# R3Mkr12F_Solar.net
KiCad netlist of a schematic drawn in EAGLE
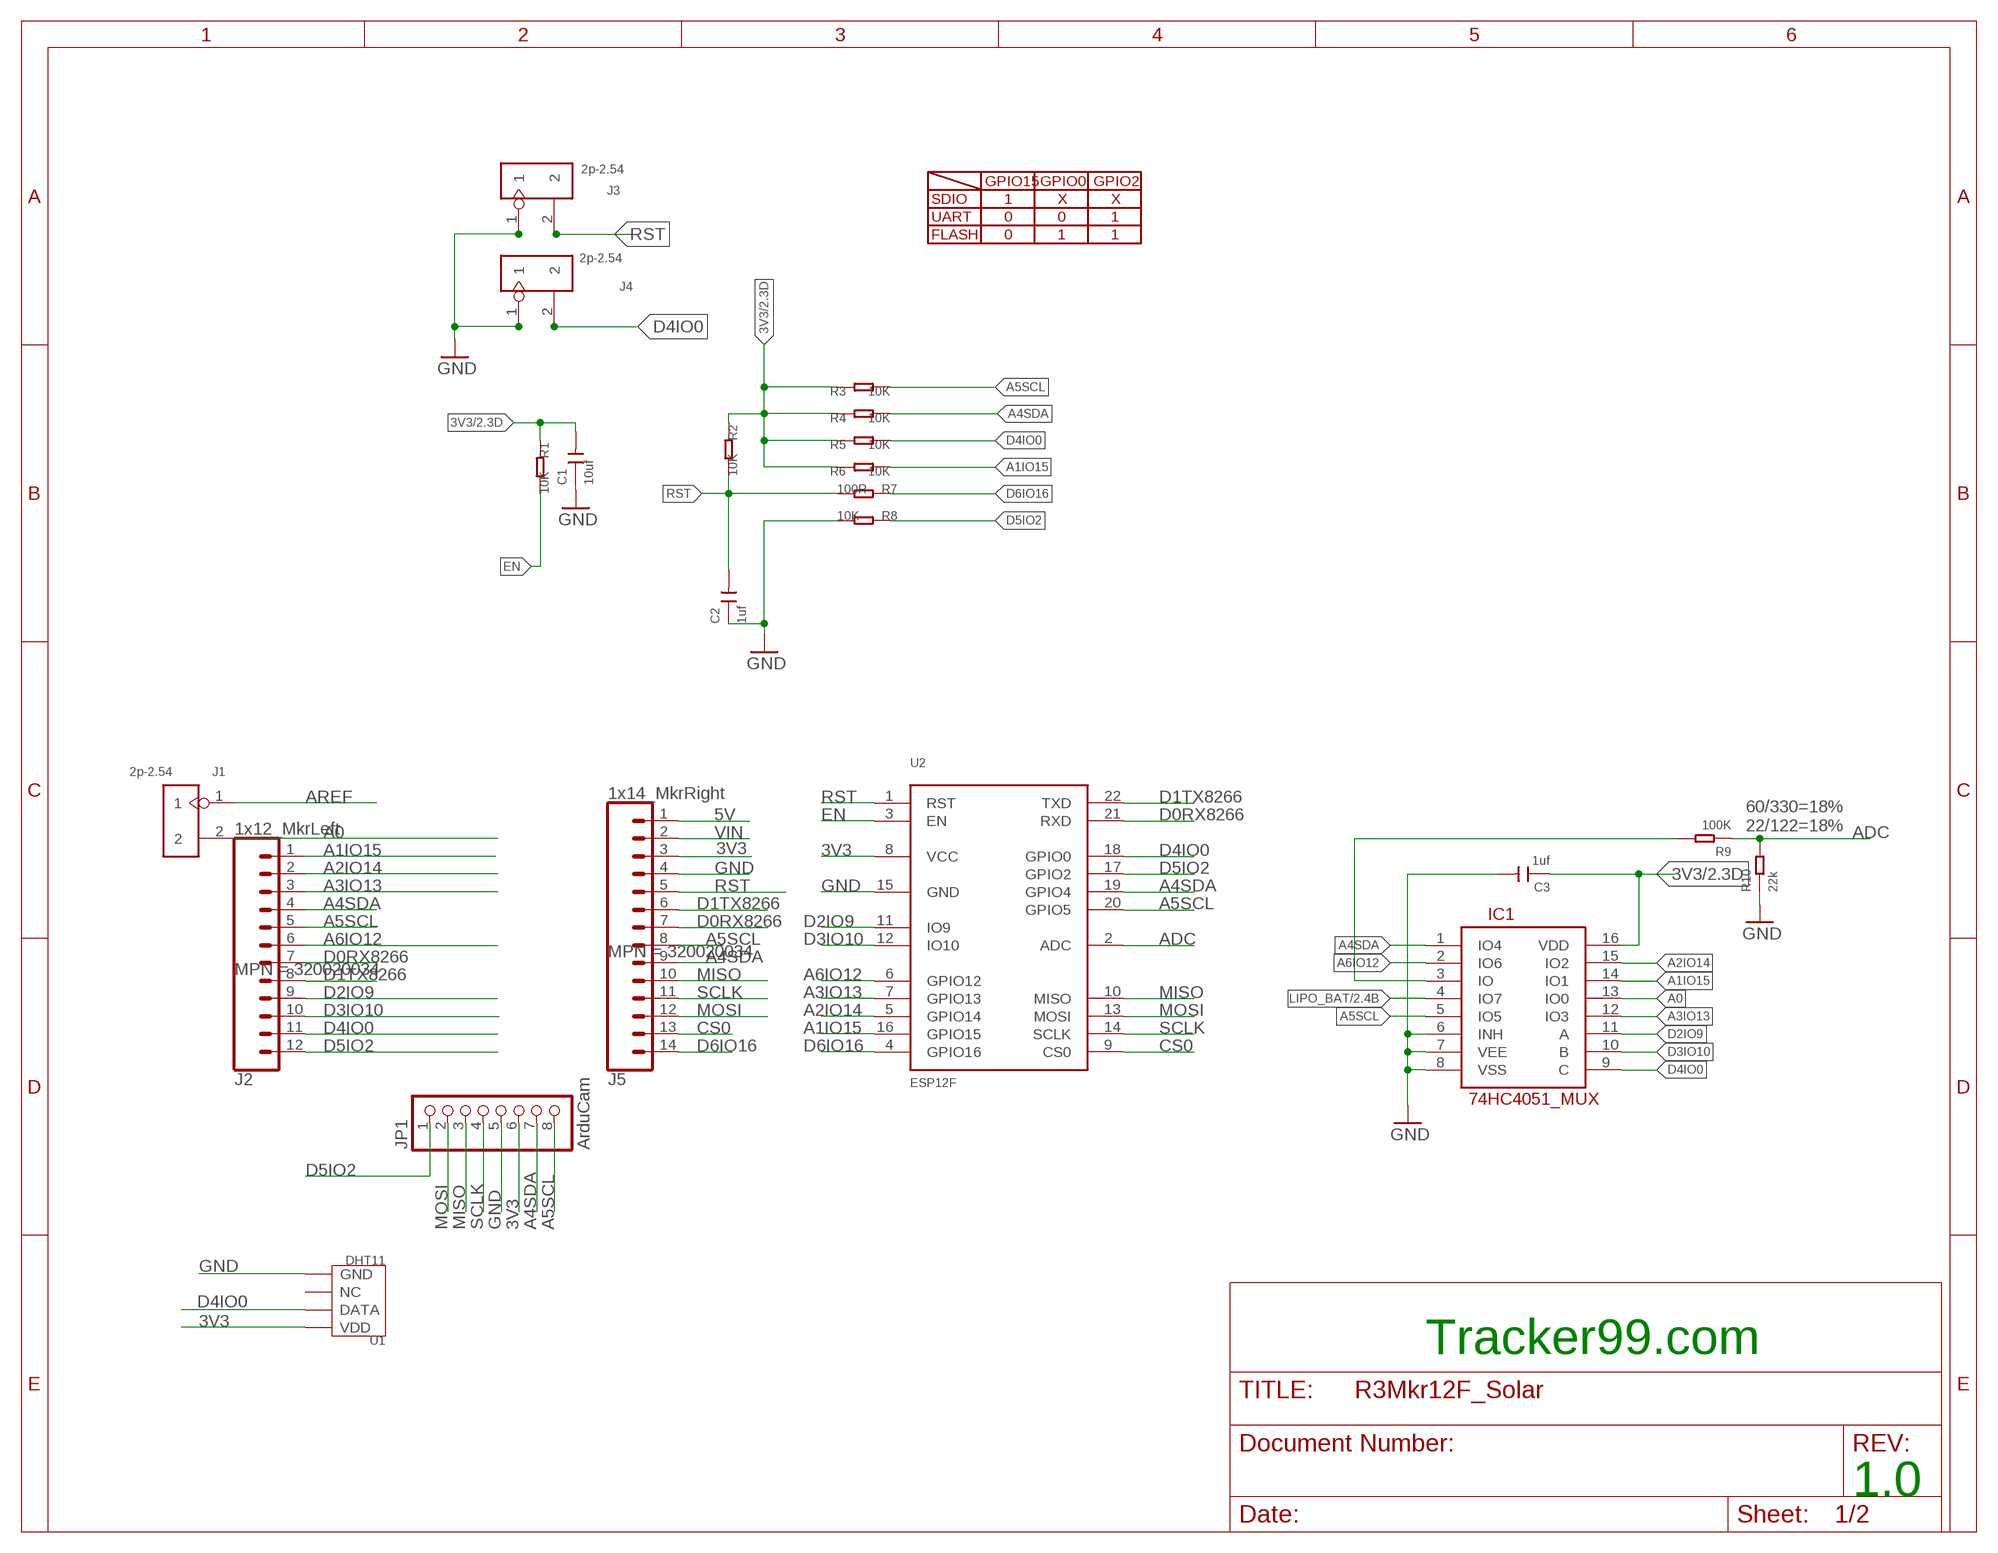
[diagram p0: schematic, sheet 1]
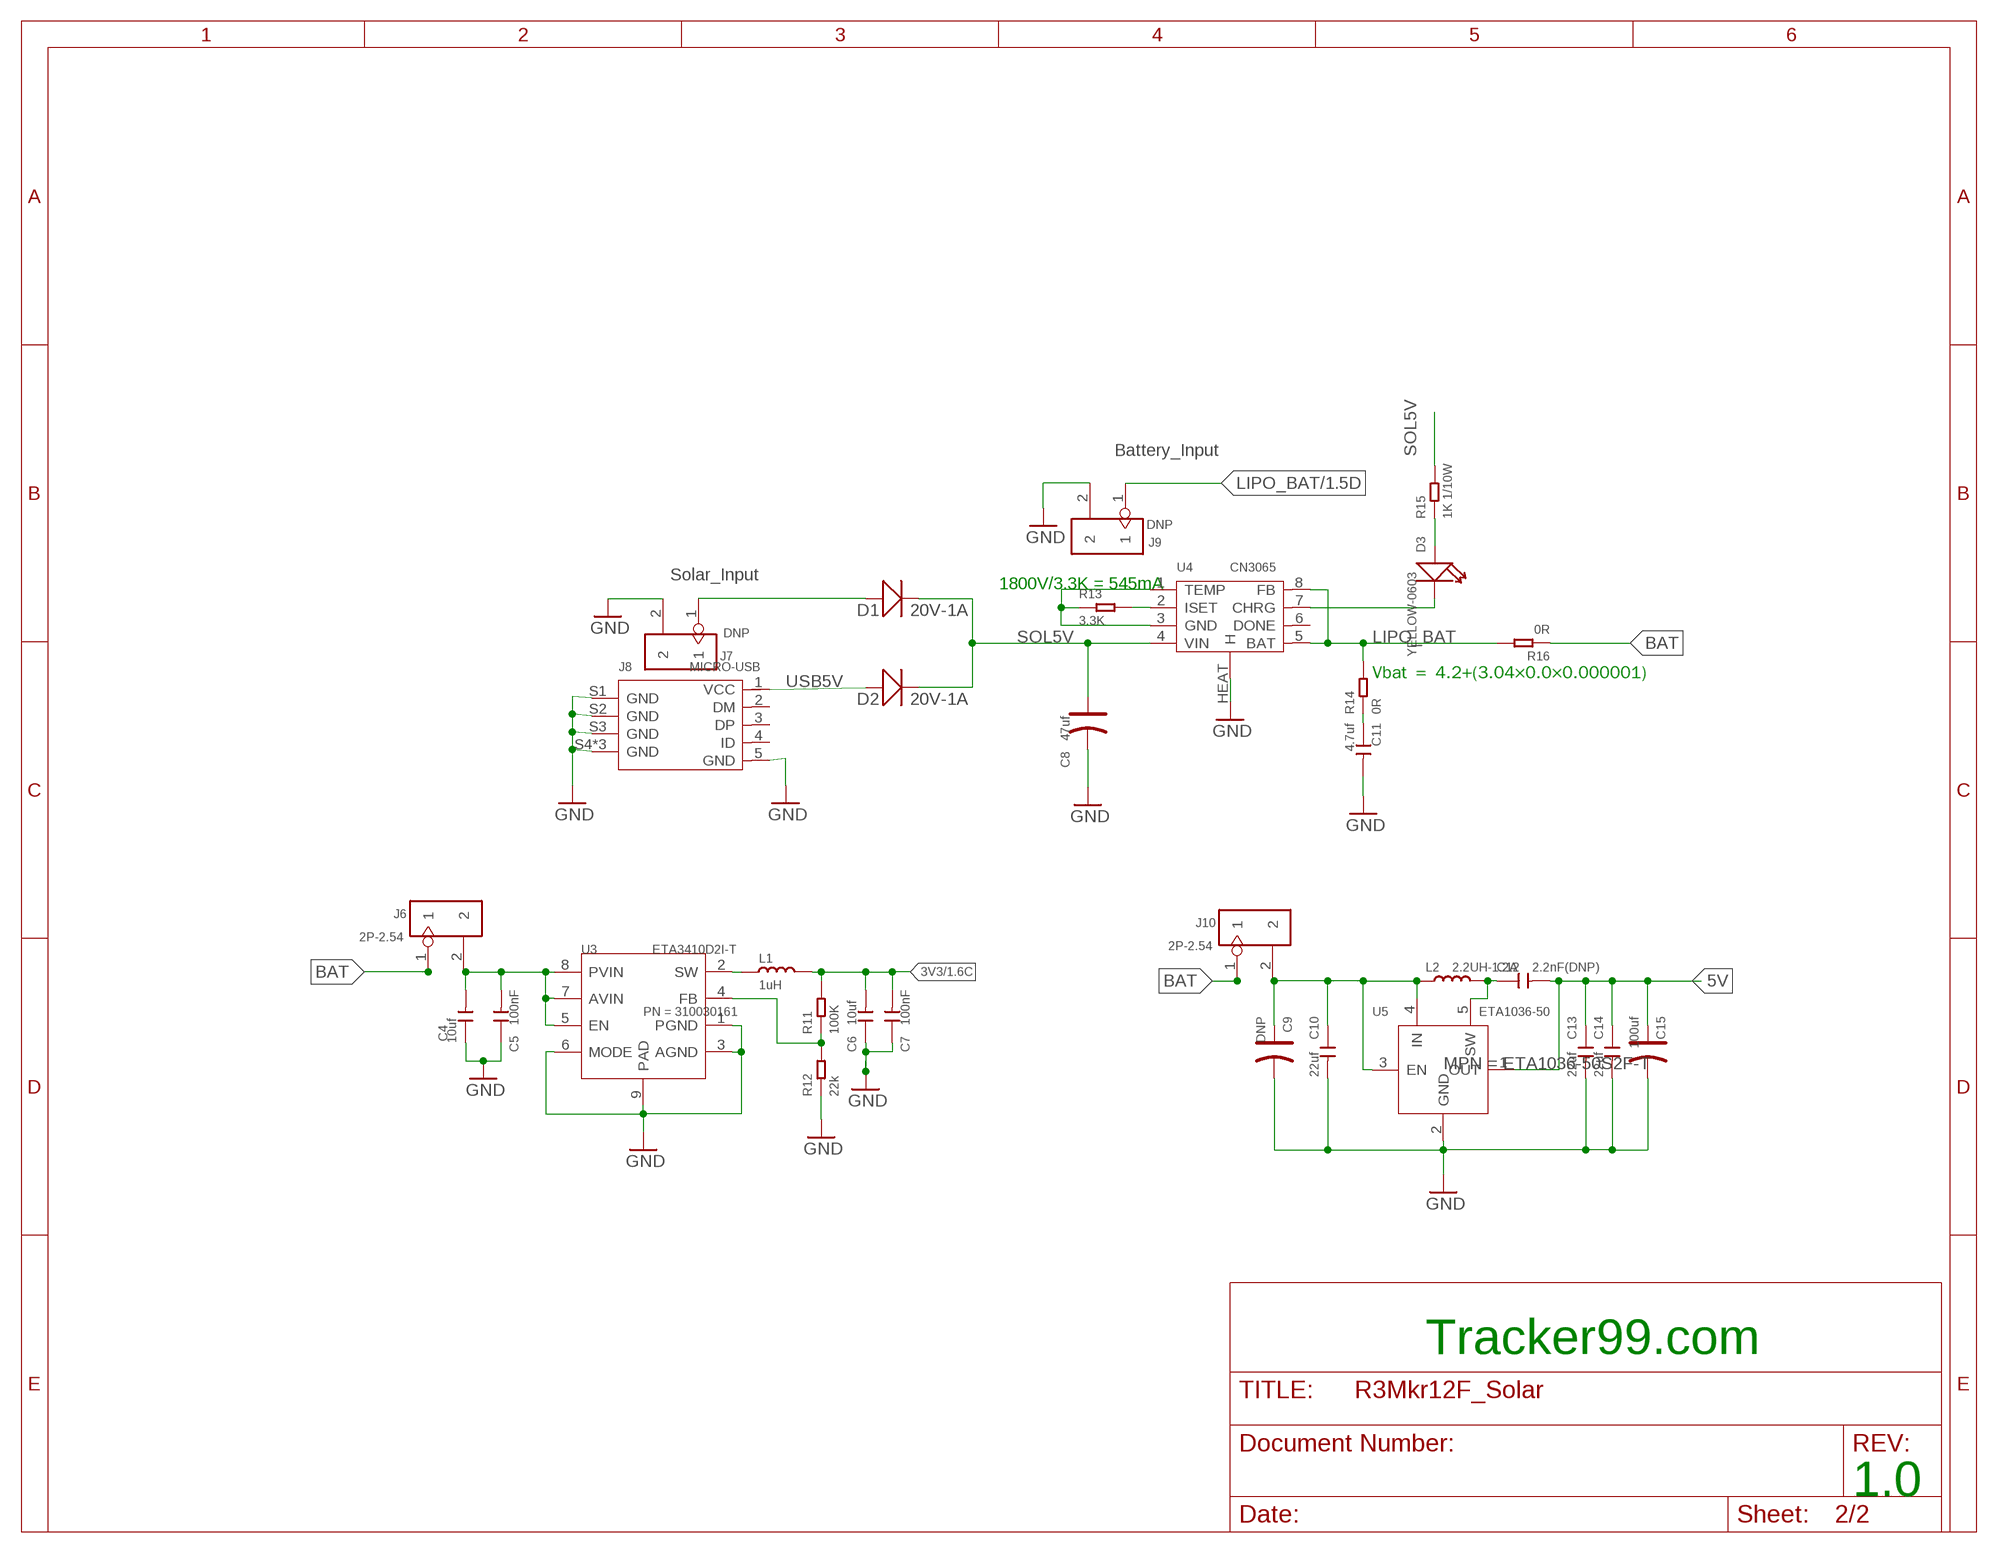
[diagram p1: schematic, sheet 2]

(export (version "E")
  (design (tool "Eeschema 10.0.6"))
  (components
    (comp (ref "C1")
      (value "10uf")
      (footprint "eagle-import:C0603")
      (fields (field (name "MPN") "CC0603KRX5R6BB106"))
      (libsource (lib "eagle-import") (part "CERAMIC-10UF-10V-10%-X5R(0603)"))
    )
    (comp (ref "C2")
      (value "1uf")
      (footprint "eagle-import:C0603")
      (fields (field (name "MPN") "CC0603KRX7R8BB105"))
      (libsource (lib "eagle-import") (part "CERAMIC-1UF-25V-10%-X7R(0603)"))
    )
    (comp (ref "C3")
      (value "1uf")
      (footprint "eagle-import:C0603")
      (fields (field (name "MPN") "CC0603KRX7R8BB105"))
      (libsource (lib "eagle-import") (part "CERAMIC-1UF-25V-10%-X7R(0603)"))
    )
    (comp (ref "IC1")
      (value "74HC4051_MUX")
      (footprint "eagle-import:SPARKFUN_SO16")
      (libsource (lib "eagle-import") (part "SPARKFUN_74HC4051_MUX"))
    )
    (comp (ref "J1")
      (value "2p-2.54")
      (footprint "eagle-import:H2-2.54")
      (fields (field (name "MPN") "RF130-1023ABS0741"))
      (libsource (lib "eagle-import") (part "DIP-BLACK-ROUND-FEMALE-HEADER-VERT(2P-2.54)"))
    )
    (comp (ref "J2")
      (value "1x12_MkrLeft")
      (footprint "eagle-import:1X12_LOCK")
      (fields (field (name "MPN") "320020034"))
      (libsource (lib "eagle-import") (part "CONN_12LOCK"))
    )
    (comp (ref "J3")
      (value "2p-2.54")
      (footprint "eagle-import:H2-2.54")
      (fields (field (name "MPN") "P125-1102A0BS116A1"))
      (libsource (lib "eagle-import") (part "DIP-BLACK-MALE-HEADER-VERT(2P-2.54)"))
    )
    (comp (ref "J4")
      (value "2p-2.54")
      (footprint "eagle-import:H2-2.54")
      (fields (field (name "MPN") "P125-1102A0BS116A1"))
      (libsource (lib "eagle-import") (part "DIP-BLACK-MALE-HEADER-VERT(2P-2.54)"))
    )
    (comp (ref "J5")
      (value "1x14_MkrRight")
      (footprint "eagle-import:1X14_LOCK")
      (fields (field (name "MPN") "320020034"))
      (libsource (lib "eagle-import") (part "CONN_14LOCK"))
    )
    (comp (ref "JP1")
      (value "ArduCam")
      (footprint "eagle-import:MILLER_1X08-LOCK")
      (libsource (lib "eagle-import") (part "MILLER_PINHD-1X8LOCK"))
    )
    (comp (ref "R1")
      (value "10K")
      (footprint "eagle-import:SEEED-RESISTOR_R0402")
      (fields (field (name "MPN") "RC0402JR-0710KL"))
      (libsource (lib "eagle-import") (part "SEEED-RESISTOR_SMD-RES-10K-5%-1/(0402)"))
    )
    (comp (ref "R2")
      (value "10K")
      (footprint "eagle-import:SEEED-RESISTOR_R0402")
      (fields (field (name "MPN") "RC0402JR-0710KL"))
      (libsource (lib "eagle-import") (part "SEEED-RESISTOR_SMD-RES-10K-5%-1/(0402)"))
    )
    (comp (ref "R3")
      (value "10K")
      (footprint "eagle-import:SEEED-RESISTOR_R0402")
      (fields (field (name "MPN") "RC0402JR-0710KL"))
      (libsource (lib "eagle-import") (part "SEEED-RESISTOR_SMD-RES-10K-5%-1/(0402)"))
    )
    (comp (ref "R4")
      (value "10K")
      (footprint "eagle-import:SEEED-RESISTOR_R0402")
      (fields (field (name "MPN") "RC0402JR-0710KL"))
      (libsource (lib "eagle-import") (part "SEEED-RESISTOR_SMD-RES-10K-5%-1/(0402)"))
    )
    (comp (ref "R5")
      (value "10K")
      (footprint "eagle-import:SEEED-RESISTOR_R0402")
      (fields (field (name "MPN") "RC0402JR-0710KL"))
      (libsource (lib "eagle-import") (part "SEEED-RESISTOR_SMD-RES-10K-5%-1/(0402)"))
    )
    (comp (ref "R6")
      (value "10K")
      (footprint "eagle-import:SEEED-RESISTOR_R0402")
      (fields (field (name "MPN") "RC0402JR-0710KL"))
      (libsource (lib "eagle-import") (part "SEEED-RESISTOR_SMD-RES-10K-5%-1/(0402)"))
    )
    (comp (ref "R7")
      (value "100R")
      (footprint "eagle-import:R0603")
      (fields (field (name "MPN") "RC0603JR-07100RL"))
      (libsource (lib "eagle-import") (part "SMD-RES-100R-5%-1/10W(0603)"))
    )
    (comp (ref "R8")
      (value "10K")
      (footprint "eagle-import:SEEED-RESISTOR_R0402")
      (fields (field (name "MPN") "RC0402JR-0710KL"))
      (libsource (lib "eagle-import") (part "SEEED-RESISTOR_SMD-RES-10K-5%-1/(0402)"))
    )
    (comp (ref "R9")
      (value "100K")
      (footprint "eagle-import:R0402")
      (fields (field (name "MPN") "RC0402FR-07100KL"))
      (libsource (lib "eagle-import") (part "SMD-RES-100K-1%-1/16W(0402)"))
    )
    (comp (ref "R10")
      (value "22k")
      (footprint "eagle-import:R0402")
      (fields (field (name "MPN") "RC0402FR-0722KL"))
      (libsource (lib "eagle-import") (part "SMD-RES-22K-1%-1/16W(0402)"))
    )
    (comp (ref "U1")
      (value "DHT11")
      (footprint "eagle-import:SNR4-2.54-15.5X12.0X5.5MM")
      (libsource (lib "eagle-import") (part "TEM-HUM-DHT11(4P-15.5X12.0MM)"))
    )
    (comp (ref "U2")
      (value "ESP12F")
      (footprint "eagle-import:ESP-12F")
      (libsource (lib "eagle-import") (part "ESP-12F"))
    )
    (comp (ref "C4")
      (value "10uf")
      (footprint "eagle-import:C0805")
      (fields (field (name "MPN") "CC0805KKX5R8BB106"))
      (libsource (lib "eagle-import") (part "CERAMIC-10UF-25V-10%-X5R(0805)"))
    )
    (comp (ref "C5")
      (value "100nF")
      (footprint "eagle-import:C0402")
      (libsource (lib "eagle-import") (part "CAP-0402"))
    )
    (comp (ref "C6")
      (value "10uf")
      (footprint "eagle-import:C0805")
      (fields (field (name "MPN") "CC0805KKX5R8BB106"))
      (libsource (lib "eagle-import") (part "CERAMIC-10UF-25V-10%-X5R(0805)"))
    )
    (comp (ref "C7")
      (value "100nF")
      (footprint "eagle-import:C0402")
      (libsource (lib "eagle-import") (part "CAP-0402"))
    )
    (comp (ref "C8")
      (value "47uf")
      (footprint "eagle-import:AVX-A")
      (fields (field (name "MPN") "TAJA476*006#NJ"))
      (libsource (lib "eagle-import") (part "TANTALUM-SMD-47UF-6.3V(AVX-A)"))
    )
    (comp (ref "C9")
      (value "DNP")
      (footprint "eagle-import:AVX-B")
      (libsource (lib "eagle-import") (part "CAP_AVX_B"))
    )
    (comp (ref "C10")
      (value "22uf")
      (footprint "eagle-import:C0805")
      (fields (field (name "MPN") "CC0805MKX5R5BB226"))
      (libsource (lib "eagle-import") (part "CERAMIC-22UF-6.3V-20%-X5R(0805)"))
    )
    (comp (ref "C11")
      (value "4.7uf")
      (footprint "eagle-import:C0603")
      (fields (field (name "MPN") "CC0603KRX5R6BB475"))
      (libsource (lib "eagle-import") (part "CERAMIC-4.7UF-10V-10%-X5R(0603)"))
    )
    (comp (ref "C12")
      (value "2.2nF(DNP)")
      (footprint "eagle-import:C0603")
      (libsource (lib "eagle-import") (part "C-0603"))
    )
    (comp (ref "C13")
      (value "22uf")
      (footprint "eagle-import:C0805")
      (fields (field (name "MPN") "CC0805MKX5R5BB226"))
      (libsource (lib "eagle-import") (part "CERAMIC-22UF-6.3V-20%-X5R(0805)"))
    )
    (comp (ref "C14")
      (value "22uf")
      (footprint "eagle-import:C0805")
      (fields (field (name "MPN") "CC0805MKX5R5BB226"))
      (libsource (lib "eagle-import") (part "CERAMIC-22UF-6.3V-20%-X5R(0805)"))
    )
    (comp (ref "C15")
      (value "100uf")
      (footprint "eagle-import:AVX-B")
      (fields (field (name "MPN") "TAJB107M010#NJ"))
      (libsource (lib "eagle-import") (part "TANTALUM-SMD-100UF-10V(AVX-B)"))
    )
    (comp (ref "D1")
      (value "20V-1A")
      (footprint "eagle-import:SOD-123")
      (fields (field (name "MPN") "B5819W"))
      (libsource (lib "eagle-import") (part "SMD-DIODE-SCHOTTKY-20V-1A(SOD-123)"))
    )
    (comp (ref "D2")
      (value "20V-1A")
      (footprint "eagle-import:SOD-123")
      (fields (field (name "MPN") "B5819W"))
      (libsource (lib "eagle-import") (part "SMD-DIODE-SCHOTTKY-20V-1A(SOD-123)"))
    )
    (comp (ref "D3")
      (value "YELLOW-0603")
      (footprint "eagle-import:LED-0603")
      (fields (field (name "MPN") "19-217-Y5C-AM1N1VY-3T"))
      (libsource (lib "eagle-import") (part "SMD-LED-CLEAR-YELLOW(0603)"))
    )
    (comp (ref "J6")
      (value "2P-2.54")
      (footprint "eagle-import:H2-2.54")
      (fields (field (name "MPN") "P125-1102A0BS116A3"))
      (libsource (lib "eagle-import") (part "DIP-WHITE-MALE-HEADER-VERT(2P-2.54)"))
    )
    (comp (ref "J7")
      (value "DNP")
      (footprint "eagle-import:H2-2.54")
      (fields (field (name "MPN") "P125-1102A0BS116A3"))
      (libsource (lib "eagle-import") (part "DIP-WHITE-MALE-HEADER-VERT(2P-2.54)"))
    )
    (comp (ref "J8")
      (value "MICRO-USB")
      (footprint "eagle-import:MICRO-USB5+4P-SMD-0.65-B")
      (fields (field (name "EAGLEUP") "USB-MICROB;2.54mm"))
      (libsource (lib "eagle-import") (part "MICRO-USB5+4P'5+4P'"))
    )
    (comp (ref "J9")
      (value "DNP")
      (footprint "eagle-import:H2-2.54")
      (fields (field (name "MPN") "P125-1102A0BS116A3"))
      (libsource (lib "eagle-import") (part "DIP-WHITE-MALE-HEADER-VERT(2P-2.54)"))
    )
    (comp (ref "J10")
      (value "2P-2.54")
      (footprint "eagle-import:H2-2.54")
      (fields (field (name "MPN") "P125-1102A0BS116A3"))
      (libsource (lib "eagle-import") (part "DIP-WHITE-MALE-HEADER-VERT(2P-2.54)"))
    )
    (comp (ref "L1")
      (value "1uH")
      (footprint "eagle-import:L0603")
      (libsource (lib "eagle-import") (part "INDUCTOR/FERRITE-BEAD'0603'"))
    )
    (comp (ref "L2")
      (value "2.2UH-1.2A")
      (footprint "eagle-import:L0805")
      (fields (field (name "MPN") "LQM2MPN2R2MG0"))
      (libsource (lib "eagle-import") (part "SMD-INDUCTOR-2.2UH-20%-1.2A(0805)"))
    )
    (comp (ref "R11")
      (value "100K")
      (footprint "eagle-import:R0402")
      (fields (field (name "MPN") "RC0402FR-07100KL"))
      (libsource (lib "eagle-import") (part "SMD-RES-100K-1%-1/16W(0402)"))
    )
    (comp (ref "R12")
      (value "22k")
      (footprint "eagle-import:R0402")
      (fields (field (name "MPN") "RC0402FR-0722KL"))
      (libsource (lib "eagle-import") (part "SMD-RES-22K-1%-1/16W(0402)"))
    )
    (comp (ref "R13")
      (value "3.3K")
      (footprint "eagle-import:R0603")
      (libsource (lib "eagle-import") (part "SMD-RES-3.3K-5%-1/10W(0603)"))
    )
    (comp (ref "R14")
      (value "0R")
      (footprint "eagle-import:R0603")
      (fields (field (name "MPN") "RC0603JR-070RL"))
      (libsource (lib "eagle-import") (part "SMD-RES-0R-5%-1/10W(0603)"))
    )
    (comp (ref "R15")
      (value "1K 1/10W")
      (footprint "eagle-import:R0603")
      (fields (field (name "MPN") "RC0603JR-071KL"))
      (libsource (lib "eagle-import") (part "SMD-RES-1K-5%-1/10W(0603)"))
    )
    (comp (ref "R16")
      (value "0R")
      (footprint "eagle-import:R0603")
      (fields (field (name "MPN") "RC0603JR-070RL"))
      (libsource (lib "eagle-import") (part "SMD-RES-0R-5%-1/10W(0603)"))
    )
    (comp (ref "U3")
      (value "ETA3410D2I-T")
      (footprint "eagle-import:DFN8G-0.5-2X2MM")
      (fields (field (name "PN") "310030161"))
      (libsource (lib "eagle-import") (part "CONVERTER-ETA3410"))
    )
    (comp (ref "U4")
      (value "CN3065")
      (footprint "eagle-import:DFN-8")
      (libsource (lib "eagle-import") (part "PMIC-CN3065-DFN8"))
    )
    (comp (ref "U5")
      (value "ETA1036-50")
      (footprint "eagle-import:SOT23-5")
      (fields (field (name "MPN") "ETA1036-50S2F-T"))
      (libsource (lib "eagle-import") (part "ETA1036"))
    )
  )
  (nets
    (net (code "1") (name "3V3") (class "Default")
      (node (ref "C1") (pin "2") (pinfunction "2_2") (pintype "passive"))
      (node (ref "C3") (pin "1") (pinfunction "1_1") (pintype "passive"))
      (node (ref "C6") (pin "2") (pinfunction "2_2") (pintype "passive"))
      (node (ref "C7") (pin "2") (pinfunction "2_2") (pintype "passive"))
      (node (ref "IC1") (pin "16") (pinfunction "VDD_16") (pintype "bidirectional"))
      (node (ref "J5") (pin "3") (pinfunction "3_3") (pintype "passive"))
      (node (ref "JP1") (pin "6") (pinfunction "6_6") (pintype "passive"))
      (node (ref "L1") (pin "2") (pinfunction "2_2") (pintype "passive"))
      (node (ref "R1") (pin "1") (pinfunction "1_1") (pintype "passive"))
      (node (ref "R11") (pin "2") (pinfunction "2_2") (pintype "passive"))
      (node (ref "R2") (pin "1") (pinfunction "1_1") (pintype "passive"))
      (node (ref "R3") (pin "1") (pinfunction "1_1") (pintype "passive"))
      (node (ref "R4") (pin "1") (pinfunction "1_1") (pintype "passive"))
      (node (ref "R5") (pin "1") (pinfunction "1_1") (pintype "passive"))
      (node (ref "R6") (pin "1") (pinfunction "1_1") (pintype "passive"))
      (node (ref "U1") (pin "1") (pinfunction "VDD_1") (pintype "power_in"))
      (node (ref "U2") (pin "8") (pinfunction "VCC_8") (pintype "bidirectional"))
    )
    (net (code "2") (name "5V") (class "Default")
      (node (ref "C12") (pin "2") (pinfunction "2_2") (pintype "passive"))
      (node (ref "C13") (pin "1") (pinfunction "1_1") (pintype "passive"))
      (node (ref "C14") (pin "1") (pinfunction "1_1") (pintype "passive"))
      (node (ref "C15") (pin "+") (pinfunction "+_+") (pintype "passive"))
      (node (ref "J5") (pin "1") (pinfunction "1_1") (pintype "passive"))
      (node (ref "U5") (pin "1") (pinfunction "OUT_1") (pintype "bidirectional"))
    )
    (net (code "3") (name "A0") (class "Default")
      (node (ref "IC1") (pin "13") (pinfunction "IO0_13") (pintype "bidirectional"))
      (node (ref "J1") (pin "2") (pinfunction "2_2") (pintype "bidirectional"))
    )
    (net (code "4") (name "A1IO15") (class "Default")
      (node (ref "IC1") (pin "14") (pinfunction "IO1_14") (pintype "bidirectional"))
      (node (ref "J2") (pin "1") (pinfunction "1_1") (pintype "passive"))
      (node (ref "R6") (pin "2") (pinfunction "2_2") (pintype "passive"))
      (node (ref "U2") (pin "16") (pinfunction "GPIO15_16") (pintype "bidirectional"))
    )
    (net (code "5") (name "A2IO14") (class "Default")
      (node (ref "IC1") (pin "15") (pinfunction "IO2_15") (pintype "bidirectional"))
      (node (ref "J2") (pin "2") (pinfunction "2_2") (pintype "passive"))
      (node (ref "U2") (pin "5") (pinfunction "GPIO14_5") (pintype "bidirectional"))
    )
    (net (code "6") (name "A3IO13") (class "Default")
      (node (ref "IC1") (pin "12") (pinfunction "IO3_12") (pintype "bidirectional"))
      (node (ref "J2") (pin "3") (pinfunction "3_3") (pintype "passive"))
      (node (ref "U2") (pin "7") (pinfunction "GPIO13_7") (pintype "bidirectional"))
    )
    (net (code "7") (name "A4SDA") (class "Default")
      (node (ref "IC1") (pin "1") (pinfunction "IO4_1") (pintype "bidirectional"))
      (node (ref "J2") (pin "4") (pinfunction "4_4") (pintype "passive"))
      (node (ref "J5") (pin "9") (pinfunction "9_9") (pintype "passive"))
      (node (ref "JP1") (pin "7") (pinfunction "7_7") (pintype "passive"))
      (node (ref "R4") (pin "2") (pinfunction "2_2") (pintype "passive"))
      (node (ref "U2") (pin "19") (pinfunction "GPIO4_19") (pintype "bidirectional"))
    )
    (net (code "8") (name "A5SCL") (class "Default")
      (node (ref "IC1") (pin "5") (pinfunction "IO5_5") (pintype "bidirectional"))
      (node (ref "J2") (pin "5") (pinfunction "5_5") (pintype "passive"))
      (node (ref "J5") (pin "8") (pinfunction "8_8") (pintype "passive"))
      (node (ref "JP1") (pin "8") (pinfunction "8_8") (pintype "passive"))
      (node (ref "R3") (pin "2") (pinfunction "2_2") (pintype "passive"))
      (node (ref "U2") (pin "20") (pinfunction "GPIO5_20") (pintype "bidirectional"))
    )
    (net (code "9") (name "A6IO12") (class "Default")
      (node (ref "IC1") (pin "2") (pinfunction "IO6_2") (pintype "bidirectional"))
      (node (ref "J2") (pin "6") (pinfunction "6_6") (pintype "passive"))
      (node (ref "U2") (pin "6") (pinfunction "GPIO12_6") (pintype "bidirectional"))
    )
    (net (code "10") (name "ADC") (class "Default")
      (node (ref "R10") (pin "2") (pinfunction "2_2") (pintype "passive"))
      (node (ref "R9") (pin "1") (pinfunction "1_1") (pintype "passive"))
      (node (ref "U2") (pin "2") (pinfunction "ADC_2") (pintype "bidirectional"))
    )
    (net (code "11") (name "AREF") (class "Default")
      (node (ref "J1") (pin "1") (pinfunction "1_1") (pintype "bidirectional"))
    )
    (net (code "12") (name "BAT") (class "Default")
      (node (ref "J10") (pin "1") (pinfunction "1_1") (pintype "bidirectional"))
      (node (ref "J6") (pin "1") (pinfunction "1_1") (pintype "bidirectional"))
      (node (ref "R16") (pin "1") (pinfunction "1_1") (pintype "passive"))
    )
    (net (code "13") (name "CS0") (class "Default")
      (node (ref "J5") (pin "13") (pinfunction "13_13") (pintype "passive"))
      (node (ref "U2") (pin "9") (pinfunction "CS0_9") (pintype "bidirectional"))
    )
    (net (code "14") (name "D0RX8266") (class "Default")
      (node (ref "J2") (pin "7") (pinfunction "7_7") (pintype "passive"))
      (node (ref "J5") (pin "7") (pinfunction "7_7") (pintype "passive"))
      (node (ref "U2") (pin "21") (pinfunction "RXD_21") (pintype "bidirectional"))
    )
    (net (code "15") (name "D1TX8266") (class "Default")
      (node (ref "J2") (pin "8") (pinfunction "8_8") (pintype "passive"))
      (node (ref "J5") (pin "6") (pinfunction "6_6") (pintype "passive"))
      (node (ref "U2") (pin "22") (pinfunction "TXD_22") (pintype "bidirectional"))
    )
    (net (code "16") (name "D2IO9") (class "Default")
      (node (ref "IC1") (pin "11") (pinfunction "A_11") (pintype "bidirectional"))
      (node (ref "J2") (pin "9") (pinfunction "9_9") (pintype "passive"))
      (node (ref "U2") (pin "11") (pinfunction "IO9_11") (pintype "bidirectional"))
    )
    (net (code "17") (name "D3IO10") (class "Default")
      (node (ref "IC1") (pin "10") (pinfunction "B_10") (pintype "bidirectional"))
      (node (ref "J2") (pin "10") (pinfunction "10_10") (pintype "passive"))
      (node (ref "U2") (pin "12") (pinfunction "IO10_12") (pintype "bidirectional"))
    )
    (net (code "18") (name "D4IO0") (class "Default")
      (node (ref "IC1") (pin "9") (pinfunction "C_9") (pintype "bidirectional"))
      (node (ref "J2") (pin "11") (pinfunction "11_11") (pintype "passive"))
      (node (ref "J4") (pin "2") (pinfunction "2_2") (pintype "bidirectional"))
      (node (ref "R5") (pin "2") (pinfunction "2_2") (pintype "passive"))
      (node (ref "U1") (pin "2") (pinfunction "DATA_2") (pintype "bidirectional"))
      (node (ref "U2") (pin "18") (pinfunction "GPIO0_18") (pintype "bidirectional"))
    )
    (net (code "19") (name "D5IO2") (class "Default")
      (node (ref "J2") (pin "12") (pinfunction "12_12") (pintype "passive"))
      (node (ref "JP1") (pin "1") (pinfunction "1_1") (pintype "passive"))
      (node (ref "R8") (pin "1") (pinfunction "1_1") (pintype "passive"))
      (node (ref "U2") (pin "17") (pinfunction "GPIO2_17") (pintype "bidirectional"))
    )
    (net (code "20") (name "D6IO16") (class "Default")
      (node (ref "J5") (pin "14") (pinfunction "14_14") (pintype "passive"))
      (node (ref "R7") (pin "1") (pinfunction "1_1") (pintype "passive"))
      (node (ref "U2") (pin "4") (pinfunction "GPIO16_4") (pintype "bidirectional"))
    )
    (net (code "21") (name "EN") (class "Default")
      (node (ref "R1") (pin "2") (pinfunction "2_2") (pintype "passive"))
      (node (ref "U2") (pin "3") (pinfunction "EN_3") (pintype "bidirectional"))
    )
    (net (code "22") (name "GND") (class "Default")
      (node (ref "C1") (pin "1") (pinfunction "1_1") (pintype "passive"))
      (node (ref "C10") (pin "2") (pinfunction "2_2") (pintype "passive"))
      (node (ref "C11") (pin "2") (pinfunction "2_2") (pintype "passive"))
      (node (ref "C13") (pin "2") (pinfunction "2_2") (pintype "passive"))
      (node (ref "C14") (pin "2") (pinfunction "2_2") (pintype "passive"))
      (node (ref "C15") (pin "-") (pinfunction "-_-") (pintype "passive"))
      (node (ref "C2") (pin "1") (pinfunction "1_1") (pintype "passive"))
      (node (ref "C3") (pin "2") (pinfunction "2_2") (pintype "passive"))
      (node (ref "C4") (pin "1") (pinfunction "1_1") (pintype "passive"))
      (node (ref "C5") (pin "1") (pinfunction "1_1") (pintype "passive"))
      (node (ref "C6") (pin "1") (pinfunction "1_1") (pintype "passive"))
      (node (ref "C7") (pin "1") (pinfunction "1_1") (pintype "passive"))
      (node (ref "C8") (pin "-") (pinfunction "-_-") (pintype "passive"))
      (node (ref "C9") (pin "-") (pinfunction "-_-") (pintype "passive"))
      (node (ref "IC1") (pin "6") (pinfunction "INH_6") (pintype "bidirectional"))
      (node (ref "IC1") (pin "7") (pinfunction "VEE_7") (pintype "bidirectional"))
      (node (ref "IC1") (pin "8") (pinfunction "VSS_8") (pintype "bidirectional"))
      (node (ref "J3") (pin "1") (pinfunction "1_1") (pintype "bidirectional"))
      (node (ref "J4") (pin "1") (pinfunction "1_1") (pintype "bidirectional"))
      (node (ref "J5") (pin "4") (pinfunction "4_4") (pintype "passive"))
      (node (ref "J7") (pin "2") (pinfunction "2_2") (pintype "bidirectional"))
      (node (ref "J8") (pin "5") (pinfunction "GND_5") (pintype "bidirectional"))
      (node (ref "J8") (pin "S1") (pinfunction "GND_S1") (pintype "bidirectional"))
      (node (ref "J8") (pin "S2") (pinfunction "GND_S2") (pintype "bidirectional"))
      (node (ref "J8") (pin "S3") (pinfunction "GND_S3") (pintype "bidirectional"))
      (node (ref "J8") (pin "S4") (pinfunction "GND_S4") (pintype "bidirectional"))
      (node (ref "J8") (pin "S5") (pinfunction "GND_S5") (pintype "bidirectional"))
      (node (ref "J8") (pin "S6") (pinfunction "GND_S6") (pintype "bidirectional"))
      (node (ref "J9") (pin "2") (pinfunction "2_2") (pintype "bidirectional"))
      (node (ref "JP1") (pin "5") (pinfunction "5_5") (pintype "passive"))
      (node (ref "R10") (pin "1") (pinfunction "1_1") (pintype "passive"))
      (node (ref "R12") (pin "1") (pinfunction "1_1") (pintype "passive"))
      (node (ref "R13") (pin "1") (pinfunction "1_1") (pintype "passive"))
      (node (ref "R8") (pin "2") (pinfunction "2_2") (pintype "passive"))
      (node (ref "U1") (pin "4") (pinfunction "GND_4") (pintype "power_in"))
      (node (ref "U2") (pin "15") (pinfunction "GND_15") (pintype "bidirectional"))
      (node (ref "U3") (pin "1") (pinfunction "PGND_1") (pintype "bidirectional"))
      (node (ref "U3") (pin "3") (pinfunction "AGND_3") (pintype "bidirectional"))
      (node (ref "U3") (pin "6") (pinfunction "MODE_6") (pintype "bidirectional"))
      (node (ref "U3") (pin "9") (pinfunction "PAD_9") (pintype "bidirectional"))
      (node (ref "U4") (pin "1") (pinfunction "TEMP_1") (pintype "input"))
      (node (ref "U4") (pin "3") (pinfunction "GND_3") (pintype "power_in"))
      (node (ref "U4") (pin "HEAT") (pinfunction "H_HEAT") (pintype "bidirectional"))
      (node (ref "U5") (pin "2") (pinfunction "GND_2") (pintype "bidirectional"))
    )
    (net (code "23") (name "LIPO_BAT") (class "Default")
      (node (ref "IC1") (pin "4") (pinfunction "IO7_4") (pintype "bidirectional"))
      (node (ref "J9") (pin "1") (pinfunction "1_1") (pintype "bidirectional"))
      (node (ref "R14") (pin "2") (pinfunction "2_2") (pintype "passive"))
      (node (ref "R16") (pin "2") (pinfunction "2_2") (pintype "passive"))
      (node (ref "U4") (pin "5") (pinfunction "BAT_5") (pintype "bidirectional"))
      (node (ref "U4") (pin "8") (pinfunction "FB_8") (pintype "input"))
    )
    (net (code "24") (name "MISO") (class "Default")
      (node (ref "J5") (pin "10") (pinfunction "10_10") (pintype "passive"))
      (node (ref "JP1") (pin "3") (pinfunction "3_3") (pintype "passive"))
      (node (ref "U2") (pin "10") (pinfunction "MISO_10") (pintype "bidirectional"))
    )
    (net (code "25") (name "MOSI") (class "Default")
      (node (ref "J5") (pin "12") (pinfunction "12_12") (pintype "passive"))
      (node (ref "JP1") (pin "2") (pinfunction "2_2") (pintype "passive"))
      (node (ref "U2") (pin "13") (pinfunction "MOSI_13") (pintype "bidirectional"))
    )
    (net (code "26") (name "Net-(C11-Pad1)") (class "Default")
      (node (ref "C11") (pin "1") (pinfunction "1_1") (pintype "passive"))
      (node (ref "R14") (pin "1") (pinfunction "1_1") (pintype "passive"))
    )
    (net (code "27") (name "Net-(D1-Pad+)") (class "Default")
      (node (ref "D1") (pin "+") (pinfunction "+_+") (pintype "passive"))
      (node (ref "J7") (pin "1") (pinfunction "1_1") (pintype "bidirectional"))
    )
    (net (code "28") (name "Net-(D3-Pad+)") (class "Default")
      (node (ref "D3") (pin "+") (pinfunction "+_+") (pintype "passive"))
      (node (ref "R15") (pin "1") (pinfunction "1_1") (pintype "passive"))
    )
    (net (code "29") (name "Net-(IC1-IO)") (class "Default")
      (node (ref "IC1") (pin "3") (pinfunction "IO_3") (pintype "bidirectional"))
      (node (ref "R9") (pin "2") (pinfunction "2_2") (pintype "passive"))
    )
    (net (code "30") (name "Net-(U3-AVIN)") (class "Default")
      (node (ref "C4") (pin "2") (pinfunction "2_2") (pintype "passive"))
      (node (ref "C5") (pin "2") (pinfunction "2_2") (pintype "passive"))
      (node (ref "J6") (pin "2") (pinfunction "2_2") (pintype "bidirectional"))
      (node (ref "U3") (pin "5") (pinfunction "EN_5") (pintype "bidirectional"))
      (node (ref "U3") (pin "7") (pinfunction "AVIN_7") (pintype "bidirectional"))
      (node (ref "U3") (pin "8") (pinfunction "PVIN_8") (pintype "bidirectional"))
    )
    (net (code "31") (name "Net-(U3-FB)") (class "Default")
      (node (ref "R11") (pin "1") (pinfunction "1_1") (pintype "passive"))
      (node (ref "R12") (pin "2") (pinfunction "2_2") (pintype "passive"))
      (node (ref "U3") (pin "4") (pinfunction "FB_4") (pintype "bidirectional"))
    )
    (net (code "32") (name "Net-(U3-SW)") (class "Default")
      (node (ref "L1") (pin "1") (pinfunction "1_1") (pintype "passive"))
      (node (ref "U3") (pin "2") (pinfunction "SW_2") (pintype "bidirectional"))
    )
    (net (code "33") (name "Net-(U4-CHRG)") (class "Default")
      (node (ref "D3") (pin "-") (pinfunction "-_-") (pintype "passive"))
      (node (ref "U4") (pin "7") (pinfunction "CHRG_7") (pintype "bidirectional"))
    )
    (net (code "34") (name "Net-(U4-ISET)") (class "Default")
      (node (ref "R13") (pin "2") (pinfunction "2_2") (pintype "passive"))
      (node (ref "U4") (pin "2") (pinfunction "ISET_2") (pintype "bidirectional"))
    )
    (net (code "35") (name "Net-(U5-EN)") (class "Default")
      (node (ref "C10") (pin "1") (pinfunction "1_1") (pintype "passive"))
      (node (ref "C9") (pin "+") (pinfunction "+_+") (pintype "passive"))
      (node (ref "J10") (pin "2") (pinfunction "2_2") (pintype "bidirectional"))
      (node (ref "L2") (pin "1") (pinfunction "1_1") (pintype "passive"))
      (node (ref "U5") (pin "3") (pinfunction "EN_3") (pintype "bidirectional"))
      (node (ref "U5") (pin "4") (pinfunction "IN_4") (pintype "bidirectional"))
    )
    (net (code "36") (name "Net-(U5-SW)") (class "Default")
      (node (ref "C12") (pin "1") (pinfunction "1_1") (pintype "passive"))
      (node (ref "L2") (pin "2") (pinfunction "2_2") (pintype "passive"))
      (node (ref "U5") (pin "5") (pinfunction "SW_5") (pintype "bidirectional"))
    )
    (net (code "37") (name "RST") (class "Default")
      (node (ref "C2") (pin "2") (pinfunction "2_2") (pintype "passive"))
      (node (ref "J3") (pin "2") (pinfunction "2_2") (pintype "bidirectional"))
      (node (ref "J5") (pin "5") (pinfunction "5_5") (pintype "passive"))
      (node (ref "R2") (pin "2") (pinfunction "2_2") (pintype "passive"))
      (node (ref "R7") (pin "2") (pinfunction "2_2") (pintype "passive"))
      (node (ref "U2") (pin "1") (pinfunction "RST_1") (pintype "bidirectional"))
    )
    (net (code "38") (name "SCLK") (class "Default")
      (node (ref "J5") (pin "11") (pinfunction "11_11") (pintype "passive"))
      (node (ref "JP1") (pin "4") (pinfunction "4_4") (pintype "passive"))
      (node (ref "U2") (pin "14") (pinfunction "SCLK_14") (pintype "bidirectional"))
    )
    (net (code "39") (name "SOL5V") (class "Default")
      (node (ref "C8") (pin "+") (pinfunction "+_+") (pintype "passive"))
      (node (ref "D1") (pin "-") (pinfunction "-_-") (pintype "passive"))
      (node (ref "D2") (pin "-") (pinfunction "-_-") (pintype "passive"))
      (node (ref "R15") (pin "2") (pinfunction "2_2") (pintype "passive"))
      (node (ref "U4") (pin "4") (pinfunction "VIN_4") (pintype "input"))
    )
    (net (code "40") (name "USB5V") (class "Default")
      (node (ref "D2") (pin "+") (pinfunction "+_+") (pintype "passive"))
      (node (ref "J8") (pin "1") (pinfunction "VCC_1") (pintype "bidirectional"))
    )
    (net (code "41") (name "VIN") (class "Default")
      (node (ref "J5") (pin "2") (pinfunction "2_2") (pintype "passive"))
    )
    (net (code "42") (name "unconnected-(J8-DM-Pad2)") (class "Default")
      (node (ref "J8") (pin "2") (pinfunction "DM_2") (pintype "bidirectional"))
    )
    (net (code "43") (name "unconnected-(J8-DP-Pad3)") (class "Default")
      (node (ref "J8") (pin "3") (pinfunction "DP_3") (pintype "bidirectional"))
    )
    (net (code "44") (name "unconnected-(J8-ID-Pad4)") (class "Default")
      (node (ref "J8") (pin "4") (pinfunction "ID_4") (pintype "bidirectional"))
    )
    (net (code "45") (name "unconnected-(U1-NC-Pad3)") (class "Default")
      (node (ref "U1") (pin "3") (pinfunction "NC_3") (pintype "no_connect"))
    )
    (net (code "46") (name "unconnected-(U4-DONE-Pad6)") (class "Default")
      (node (ref "U4") (pin "6") (pinfunction "DONE_6") (pintype "bidirectional"))
    )
  )
)
